# VFD_alpha_Sheet2.net
KiCad netlist of a schematic drawn in Altium Designer
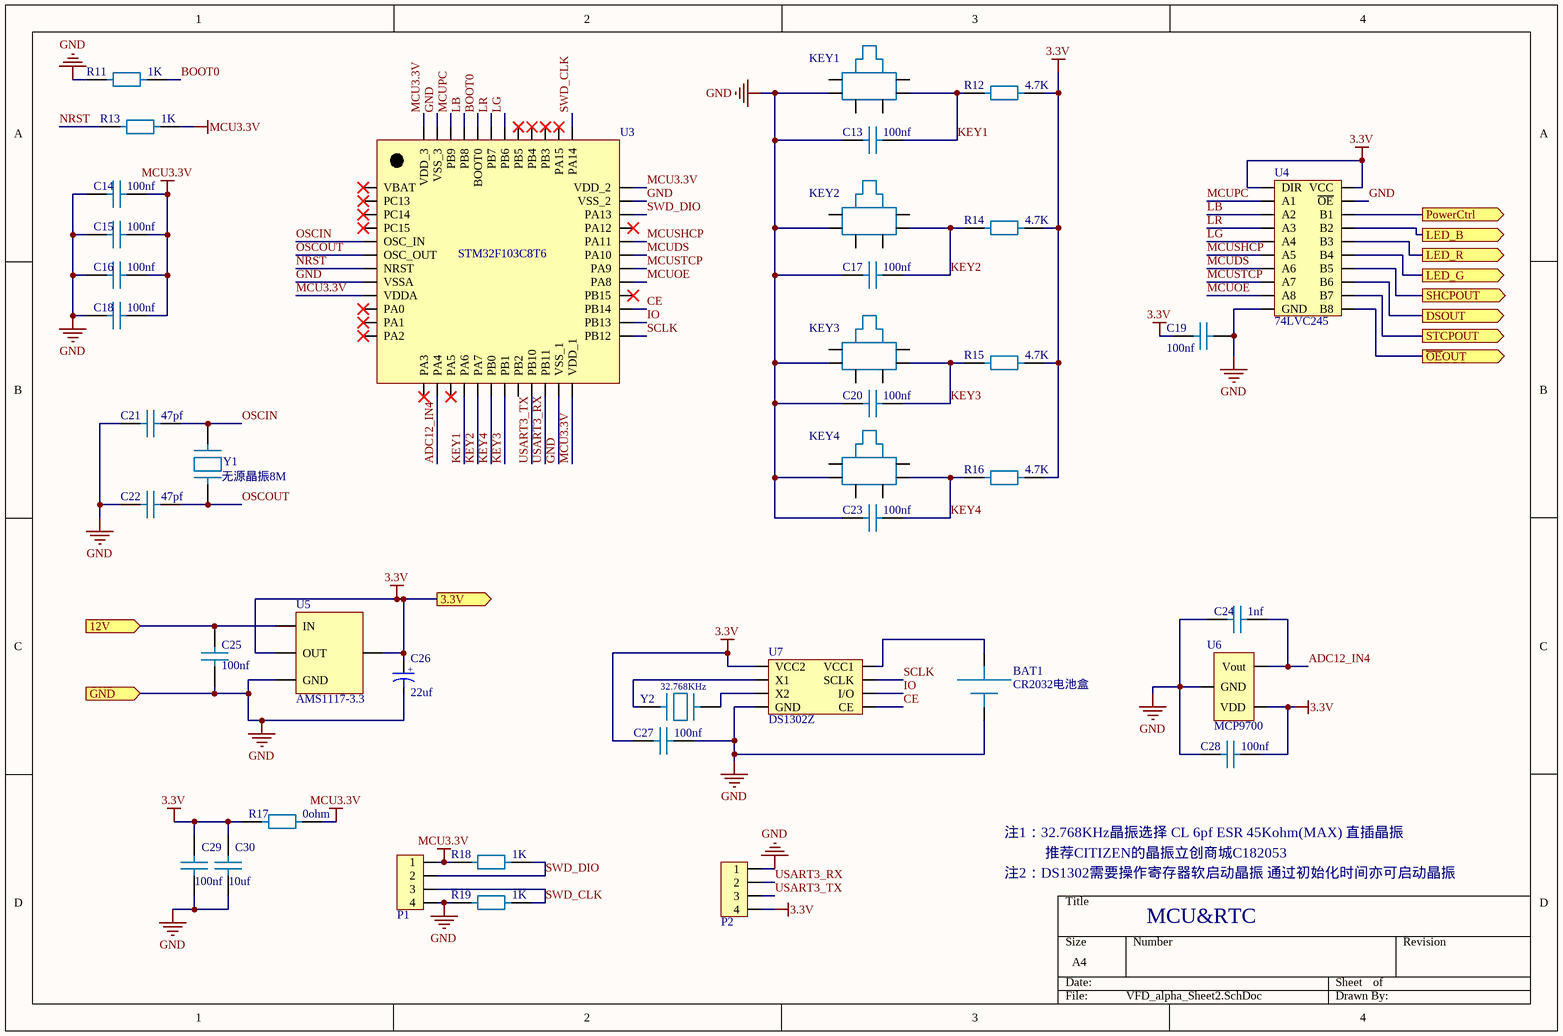
[diagram p0: VFD_alpha_Sheet2.SchDoc]

(export (version "E")
  (design (tool "Eeschema 10.0.6"))
  (components
    (comp (ref "BAT1")
      (value "CR2032电池盒")
      (footprint "SBAT-CR2032")
      (libsource (lib "ZZB_Lib") (part "CR2032电池盒"))
    )
    (comp (ref "C13")
      (value "100nf")
      (footprint "0603")
      (fields (field (name "Comment") "C"))
      (libsource (lib "ZZB_Lib") (part "C(0603)"))
    )
    (comp (ref "C14")
      (value "100nf")
      (footprint "0603")
      (fields (field (name "Comment") "C"))
      (libsource (lib "ZZB_Lib") (part "C(0603)"))
    )
    (comp (ref "C15")
      (value "100nf")
      (footprint "0603")
      (fields (field (name "Comment") "C"))
      (libsource (lib "ZZB_Lib") (part "C(0603)"))
    )
    (comp (ref "C16")
      (value "100nf")
      (footprint "0603")
      (fields (field (name "Comment") "C"))
      (libsource (lib "ZZB_Lib") (part "C(0603)"))
    )
    (comp (ref "C17")
      (value "100nf")
      (footprint "0603")
      (fields (field (name "Comment") "C"))
      (libsource (lib "ZZB_Lib") (part "C(0603)"))
    )
    (comp (ref "C18")
      (value "100nf")
      (footprint "0603")
      (fields (field (name "Comment") "C"))
      (libsource (lib "ZZB_Lib") (part "C(0603)"))
    )
    (comp (ref "C19")
      (value "100nf")
      (footprint "0603")
      (fields (field (name "Comment") "C"))
      (libsource (lib "ZZB_Lib") (part "C(0603)"))
    )
    (comp (ref "C20")
      (value "100nf")
      (footprint "0603")
      (fields (field (name "Comment") "C"))
      (libsource (lib "ZZB_Lib") (part "C(0603)"))
    )
    (comp (ref "C21")
      (value "47pf")
      (footprint "0603")
      (fields (field (name "Comment") "C"))
      (libsource (lib "ZZB_Lib") (part "C(0603)"))
    )
    (comp (ref "C22")
      (value "47pf")
      (footprint "0603")
      (fields (field (name "Comment") "C"))
      (libsource (lib "ZZB_Lib") (part "C(0603)"))
    )
    (comp (ref "C23")
      (value "100nf")
      (footprint "0603")
      (fields (field (name "Comment") "C"))
      (libsource (lib "ZZB_Lib") (part "C(0603)"))
    )
    (comp (ref "C24")
      (value "1nf")
      (footprint "0603")
      (fields (field (name "Comment") "C"))
      (libsource (lib "ZZB_Lib") (part "C(0603)"))
    )
    (comp (ref "C25")
      (value "100nf")
      (footprint "0805")
      (fields (field (name "Comment") "C(0805)"))
      (libsource (lib "ZZB_Lib") (part "C(0805)"))
    )
    (comp (ref "C26")
      (value "22uf")
      (footprint "CAPCP3216X06N")
      (fields (field (name "Comment") "钽电容"))
      (libsource (lib "ZZB_Lib") (part "钽电容(3216)"))
    )
    (comp (ref "C27")
      (value "100nf")
      (footprint "0603")
      (fields (field (name "Comment") "C"))
      (libsource (lib "ZZB_Lib") (part "C(0603)"))
    )
    (comp (ref "C28")
      (value "100nf")
      (footprint "0603")
      (fields (field (name "Comment") "C"))
      (libsource (lib "ZZB_Lib") (part "C(0603)"))
    )
    (comp (ref "C29")
      (value "100nf")
      (footprint "0603")
      (fields (field (name "Comment") "C"))
      (libsource (lib "ZZB_Lib") (part "C(0603)"))
    )
    (comp (ref "C30")
      (value "10uf")
      (footprint "0603")
      (fields (field (name "Comment") "C"))
      (libsource (lib "ZZB_Lib") (part "C(0603)"))
    )
    (comp (ref "KEY1") (value "无锁按键") (footprint "侧面按键") (libsource (lib "ZZB_Lib") (part "无锁按键")))
    (comp (ref "KEY2") (value "无锁按键") (footprint "侧面按键") (libsource (lib "ZZB_Lib") (part "无锁按键")))
    (comp (ref "KEY3") (value "无锁按键") (footprint "侧面按键") (libsource (lib "ZZB_Lib") (part "无锁按键")))
    (comp (ref "KEY4") (value "无锁按键") (footprint "侧面按键") (libsource (lib "ZZB_Lib") (part "无锁按键")))
    (comp (ref "P1") (value "连接器4P") (footprint "Connector4P") (libsource (lib "ZZB_Lib") (part "连接器4P")))
    (comp (ref "P2") (value "连接器4P") (footprint "Connector4P") (libsource (lib "ZZB_Lib") (part "连接器4P")))
    (comp (ref "R11")
      (value "1K")
      (footprint "0603")
      (fields (field (name "Comment") "R"))
      (libsource (lib "ZZB_Lib") (part "R(0603)"))
    )
    (comp (ref "R12")
      (value "4.7K")
      (footprint "0603")
      (fields (field (name "Comment") "R"))
      (libsource (lib "ZZB_Lib") (part "R(0603)"))
    )
    (comp (ref "R13")
      (value "1K")
      (footprint "0603")
      (fields (field (name "Comment") "R"))
      (libsource (lib "ZZB_Lib") (part "R(0603)"))
    )
    (comp (ref "R14")
      (value "4.7K")
      (footprint "0603")
      (fields (field (name "Comment") "R"))
      (libsource (lib "ZZB_Lib") (part "R(0603)"))
    )
    (comp (ref "R15")
      (value "4.7K")
      (footprint "0603")
      (fields (field (name "Comment") "R"))
      (libsource (lib "ZZB_Lib") (part "R(0603)"))
    )
    (comp (ref "R16")
      (value "4.7K")
      (footprint "0603")
      (fields (field (name "Comment") "R"))
      (libsource (lib "ZZB_Lib") (part "R(0603)"))
    )
    (comp (ref "R17")
      (value "0ohm")
      (footprint "0603")
      (fields (field (name "Comment") "R"))
      (libsource (lib "ZZB_Lib") (part "R(0603)"))
    )
    (comp (ref "R18")
      (value "1K")
      (footprint "0603")
      (fields (field (name "Comment") "R"))
      (libsource (lib "ZZB_Lib") (part "R(0603)"))
    )
    (comp (ref "R19")
      (value "1K")
      (footprint "0603")
      (fields (field (name "Comment") "R"))
      (libsource (lib "ZZB_Lib") (part "R(0603)"))
    )
    (comp (ref "U3")
      (value "STM32F103C8T6")
      (footprint "STM32F103x8LQFP48")
      (libsource (lib "ZZB_Lib") (part "STM32F103C8T6"))
    )
    (comp (ref "U4")
      (value "74LVC245")
      (footprint "TSOP-20N-74LVC245")
      (libsource (lib "ZZB_Lib") (part "74LVC245"))
    )
    (comp (ref "U5")
      (value "AMS1117-3.3")
      (footprint "AMS1117-3.3")
      (libsource (lib "ZZB_Lib") (part "AMS1117-X"))
    )
    (comp (ref "U6")
      (value "MCP9700")
      (footprint "SOT-23-s8550")
      (libsource (lib "ZZB_Lib") (part "MCP9700"))
    )
    (comp (ref "U7")
      (value "DS1302Z")
      (footprint "SOIC-8P DS1302Z")
      (libsource (lib "ZZB_Lib") (part "DS1302Z"))
    )
    (comp (ref "Y1") (value "无源晶振8M") (footprint "晶振8M") (libsource (lib "ZZB_Lib") (part "无源晶振8M")))
    (comp (ref "Y2")
      (value "直插无源晶振32.768KHz")
      (footprint "2*6_OSC")
      (libsource (lib "ZZB_Lib") (part "直插无源晶振32.768KHz"))
    )
  )
  (nets
    (net (code "1") (name "/12V") (class "Default")
      (node (ref "C25") (pin "2") (pinfunction "2_2") (pintype "passive"))
      (node (ref "U5") (pin "3") (pinfunction "IN_3") (pintype "passive"))
    )
    (net (code "2") (name "/ADC12_IN4") (class "Default")
      (node (ref "C24") (pin "2") (pinfunction "2_2") (pintype "passive"))
      (node (ref "U3") (pin "14") (pinfunction "PA4_14") (pintype "passive"))
      (node (ref "U6") (pin "3") (pinfunction "Vout_3") (pintype "passive"))
    )
    (net (code "3") (name "/BOOT0") (class "Default")
      (node (ref "R11") (pin "1") (pinfunction "1_1") (pintype "passive"))
      (node (ref "U3") (pin "44") (pinfunction "BOOT0_44") (pintype "passive"))
    )
    (net (code "4") (name "/CE") (class "Default")
      (node (ref "U3") (pin "27") (pinfunction "PB14_27") (pintype "passive"))
      (node (ref "U7") (pin "5") (pinfunction "CE_5") (pintype "passive"))
    )
    (net (code "5") (name "/DSOUT") (class "Default")
      (node (ref "U4") (pin "13") (pinfunction "B6_13") (pintype "passive"))
    )
    (net (code "6") (name "/IO") (class "Default")
      (node (ref "U3") (pin "26") (pinfunction "PB13_26") (pintype "passive"))
      (node (ref "U7") (pin "6") (pinfunction "I/O_6") (pintype "passive"))
    )
    (net (code "7") (name "/KEY1") (class "Default")
      (node (ref "C13") (pin "2") (pinfunction "2_2") (pintype "passive"))
      (node (ref "KEY1") (pin "5") (pinfunction "5_5") (pintype "passive"))
      (node (ref "R12") (pin "1") (pinfunction "1_1") (pintype "passive"))
      (node (ref "U3") (pin "16") (pinfunction "PA6_16") (pintype "passive"))
    )
    (net (code "8") (name "/KEY2") (class "Default")
      (node (ref "C17") (pin "2") (pinfunction "2_2") (pintype "passive"))
      (node (ref "KEY2") (pin "5") (pinfunction "5_5") (pintype "passive"))
      (node (ref "R14") (pin "1") (pinfunction "1_1") (pintype "passive"))
      (node (ref "U3") (pin "17") (pinfunction "PA7_17") (pintype "passive"))
    )
    (net (code "9") (name "/KEY3") (class "Default")
      (node (ref "C20") (pin "2") (pinfunction "2_2") (pintype "passive"))
      (node (ref "KEY3") (pin "5") (pinfunction "5_5") (pintype "passive"))
      (node (ref "R15") (pin "1") (pinfunction "1_1") (pintype "passive"))
      (node (ref "U3") (pin "19") (pinfunction "PB1_19") (pintype "passive"))
    )
    (net (code "10") (name "/KEY4") (class "Default")
      (node (ref "C23") (pin "2") (pinfunction "2_2") (pintype "passive"))
      (node (ref "KEY4") (pin "5") (pinfunction "5_5") (pintype "passive"))
      (node (ref "R16") (pin "1") (pinfunction "1_1") (pintype "passive"))
      (node (ref "U3") (pin "18") (pinfunction "PB0_18") (pintype "passive"))
    )
    (net (code "11") (name "/LB") (class "Default")
      (node (ref "U3") (pin "45") (pinfunction "PB8_45") (pintype "passive"))
      (node (ref "U4") (pin "3") (pinfunction "A2_3") (pintype "passive"))
    )
    (net (code "12") (name "/LED_B") (class "Default")
      (node (ref "U4") (pin "17") (pinfunction "B2_17") (pintype "passive"))
    )
    (net (code "13") (name "/LED_G") (class "Default")
      (node (ref "U4") (pin "15") (pinfunction "B4_15") (pintype "passive"))
    )
    (net (code "14") (name "/LED_R") (class "Default")
      (node (ref "U4") (pin "16") (pinfunction "B3_16") (pintype "passive"))
    )
    (net (code "15") (name "/LG") (class "Default")
      (node (ref "U3") (pin "42") (pinfunction "PB6_42") (pintype "passive"))
      (node (ref "U4") (pin "5") (pinfunction "A4_5") (pintype "passive"))
    )
    (net (code "16") (name "/LR") (class "Default")
      (node (ref "U3") (pin "43") (pinfunction "PB7_43") (pintype "passive"))
      (node (ref "U4") (pin "4") (pinfunction "A3_4") (pintype "passive"))
    )
    (net (code "17") (name "/MCUDS") (class "Default")
      (node (ref "U3") (pin "31") (pinfunction "PA10_31") (pintype "passive"))
      (node (ref "U4") (pin "7") (pinfunction "A6_7") (pintype "passive"))
    )
    (net (code "18") (name "/MCUOE") (class "Default")
      (node (ref "U3") (pin "29") (pinfunction "PA8_29") (pintype "passive"))
      (node (ref "U4") (pin "9") (pinfunction "A8_9") (pintype "passive"))
    )
    (net (code "19") (name "/MCUPC") (class "Default")
      (node (ref "U3") (pin "46") (pinfunction "PB9_46") (pintype "passive"))
      (node (ref "U4") (pin "2") (pinfunction "A1_2") (pintype "passive"))
    )
    (net (code "20") (name "/MCUSHCP") (class "Default")
      (node (ref "U3") (pin "32") (pinfunction "PA11_32") (pintype "passive"))
      (node (ref "U4") (pin "6") (pinfunction "A5_6") (pintype "passive"))
    )
    (net (code "21") (name "/MCUSTCP") (class "Default")
      (node (ref "U3") (pin "30") (pinfunction "PA9_30") (pintype "passive"))
      (node (ref "U4") (pin "8") (pinfunction "A7_8") (pintype "passive"))
    )
    (net (code "22") (name "/NRST") (class "Default")
      (node (ref "R13") (pin "1") (pinfunction "1_1") (pintype "passive"))
      (node (ref "U3") (pin "7") (pinfunction "NRST_7") (pintype "passive"))
    )
    (net (code "23") (name "/OSCIN") (class "Default")
      (node (ref "C21") (pin "2") (pinfunction "2_2") (pintype "passive"))
      (node (ref "U3") (pin "5") (pinfunction "OSC_IN_5") (pintype "passive"))
      (node (ref "Y1") (pin "2") (pinfunction "2_2") (pintype "passive"))
    )
    (net (code "24") (name "/OSCOUT") (class "Default")
      (node (ref "C22") (pin "2") (pinfunction "2_2") (pintype "passive"))
      (node (ref "U3") (pin "6") (pinfunction "OSC_OUT_6") (pintype "passive"))
      (node (ref "Y1") (pin "1") (pinfunction "1_1") (pintype "passive"))
    )
    (net (code "25") (name "/PowerCtrl") (class "Default")
      (node (ref "U4") (pin "18") (pinfunction "B1_18") (pintype "passive"))
    )
    (net (code "26") (name "/SCLK") (class "Default")
      (node (ref "U3") (pin "25") (pinfunction "PB12_25") (pintype "passive"))
      (node (ref "U7") (pin "7") (pinfunction "SCLK_7") (pintype "passive"))
    )
    (net (code "27") (name "/SHCPOUT") (class "Default")
      (node (ref "U4") (pin "14") (pinfunction "B5_14") (pintype "passive"))
    )
    (net (code "28") (name "/STCPOUT") (class "Default")
      (node (ref "U4") (pin "12") (pinfunction "B7_12") (pintype "passive"))
    )
    (net (code "29") (name "/SWD_CLK") (class "Default")
      (node (ref "P1") (pin "3") (pinfunction "3_3") (pintype "passive"))
      (node (ref "R19") (pin "2") (pinfunction "2_2") (pintype "passive"))
      (node (ref "U3") (pin "37") (pinfunction "PA14_37") (pintype "passive"))
    )
    (net (code "30") (name "/SWD_DIO") (class "Default")
      (node (ref "P1") (pin "2") (pinfunction "2_2") (pintype "passive"))
      (node (ref "R18") (pin "1") (pinfunction "1_1") (pintype "passive"))
      (node (ref "U3") (pin "34") (pinfunction "PA13_34") (pintype "passive"))
    )
    (net (code "31") (name "/USART3_RX") (class "Default")
      (node (ref "P2") (pin "2") (pinfunction "2_2") (pintype "passive"))
      (node (ref "U3") (pin "22") (pinfunction "PB11_22") (pintype "passive"))
    )
    (net (code "32") (name "/USART3_TX") (class "Default")
      (node (ref "P2") (pin "3") (pinfunction "3_3") (pintype "passive"))
      (node (ref "U3") (pin "21") (pinfunction "PB10_21") (pintype "passive"))
    )
    (net (code "33") (name "/~{OE}OUT") (class "Default")
      (node (ref "U4") (pin "11") (pinfunction "B8_11") (pintype "passive"))
    )
    (net (code "34") (name "3.3V") (class "Default")
      (node (ref "C19") (pin "1") (pinfunction "1_1") (pintype "passive"))
      (node (ref "C26") (pin "1") (pinfunction "1_1") (pintype "passive"))
      (node (ref "C27") (pin "1") (pinfunction "1_1") (pintype "passive"))
      (node (ref "C28") (pin "2") (pinfunction "2_2") (pintype "passive"))
      (node (ref "C29") (pin "2") (pinfunction "2_2") (pintype "passive"))
      (node (ref "C30") (pin "2") (pinfunction "2_2") (pintype "passive"))
      (node (ref "P2") (pin "4") (pinfunction "4_4") (pintype "passive"))
      (node (ref "R12") (pin "2") (pinfunction "2_2") (pintype "passive"))
      (node (ref "R14") (pin "2") (pinfunction "2_2") (pintype "passive"))
      (node (ref "R15") (pin "2") (pinfunction "2_2") (pintype "passive"))
      (node (ref "R16") (pin "2") (pinfunction "2_2") (pintype "passive"))
      (node (ref "R17") (pin "1") (pinfunction "1_1") (pintype "passive"))
      (node (ref "U4") (pin "1") (pinfunction "DIR_1") (pintype "passive"))
      (node (ref "U4") (pin "20") (pinfunction "VCC_20") (pintype "passive"))
      (node (ref "U5") (pin "2") (pinfunction "OUT_2") (pintype "passive"))
      (node (ref "U5") (pin "4") (pintype "passive"))
      (node (ref "U6") (pin "1") (pinfunction "VDD_1") (pintype "passive"))
      (node (ref "U7") (pin "1") (pinfunction "VCC2_1") (pintype "passive"))
    )
    (net (code "35") (name "GND") (class "Default")
      (node (ref "BAT1") (pin "1") (pinfunction "1_1") (pintype "passive"))
      (node (ref "C13") (pin "1") (pinfunction "1_1") (pintype "passive"))
      (node (ref "C14") (pin "1") (pinfunction "1_1") (pintype "passive"))
      (node (ref "C15") (pin "1") (pinfunction "1_1") (pintype "passive"))
      (node (ref "C16") (pin "1") (pinfunction "1_1") (pintype "passive"))
      (node (ref "C17") (pin "1") (pinfunction "1_1") (pintype "passive"))
      (node (ref "C18") (pin "1") (pinfunction "1_1") (pintype "passive"))
      (node (ref "C19") (pin "2") (pinfunction "2_2") (pintype "passive"))
      (node (ref "C20") (pin "1") (pinfunction "1_1") (pintype "passive"))
      (node (ref "C21") (pin "1") (pinfunction "1_1") (pintype "passive"))
      (node (ref "C22") (pin "1") (pinfunction "1_1") (pintype "passive"))
      (node (ref "C23") (pin "1") (pinfunction "1_1") (pintype "passive"))
      (node (ref "C24") (pin "1") (pinfunction "1_1") (pintype "passive"))
      (node (ref "C25") (pin "1") (pinfunction "1_1") (pintype "passive"))
      (node (ref "C26") (pin "2") (pinfunction "2_2") (pintype "passive"))
      (node (ref "C27") (pin "2") (pinfunction "2_2") (pintype "passive"))
      (node (ref "C28") (pin "1") (pinfunction "1_1") (pintype "passive"))
      (node (ref "C29") (pin "1") (pinfunction "1_1") (pintype "passive"))
      (node (ref "C30") (pin "1") (pinfunction "1_1") (pintype "passive"))
      (node (ref "KEY1") (pin "2") (pinfunction "2_2") (pintype "passive"))
      (node (ref "KEY2") (pin "2") (pinfunction "2_2") (pintype "passive"))
      (node (ref "KEY3") (pin "2") (pinfunction "2_2") (pintype "passive"))
      (node (ref "KEY4") (pin "2") (pinfunction "2_2") (pintype "passive"))
      (node (ref "P1") (pin "4") (pinfunction "4_4") (pintype "passive"))
      (node (ref "P2") (pin "1") (pinfunction "1_1") (pintype "passive"))
      (node (ref "R11") (pin "2") (pinfunction "2_2") (pintype "passive"))
      (node (ref "R19") (pin "1") (pinfunction "1_1") (pintype "passive"))
      (node (ref "U3") (pin "23") (pinfunction "VSS_1_23") (pintype "passive"))
      (node (ref "U3") (pin "35") (pinfunction "VSS_2_35") (pintype "passive"))
      (node (ref "U3") (pin "47") (pinfunction "VSS_3_47") (pintype "passive"))
      (node (ref "U3") (pin "8") (pinfunction "VSSA_8") (pintype "passive"))
      (node (ref "U4") (pin "10") (pinfunction "GND_10") (pintype "passive"))
      (node (ref "U4") (pin "19") (pinfunction "~{OE}_19") (pintype "passive"))
      (node (ref "U5") (pin "1") (pinfunction "GND_1") (pintype "passive"))
      (node (ref "U6") (pin "2") (pinfunction "GND_2") (pintype "passive"))
      (node (ref "U7") (pin "4") (pinfunction "GND_4") (pintype "passive"))
    )
    (net (code "36") (name "MCU3.3V") (class "Default")
      (node (ref "C14") (pin "2") (pinfunction "2_2") (pintype "passive"))
      (node (ref "C15") (pin "2") (pinfunction "2_2") (pintype "passive"))
      (node (ref "C16") (pin "2") (pinfunction "2_2") (pintype "passive"))
      (node (ref "C18") (pin "2") (pinfunction "2_2") (pintype "passive"))
      (node (ref "P1") (pin "1") (pinfunction "1_1") (pintype "passive"))
      (node (ref "R13") (pin "2") (pinfunction "2_2") (pintype "passive"))
      (node (ref "R17") (pin "2") (pinfunction "2_2") (pintype "passive"))
      (node (ref "R18") (pin "2") (pinfunction "2_2") (pintype "passive"))
      (node (ref "U3") (pin "24") (pinfunction "VDD_1_24") (pintype "passive"))
      (node (ref "U3") (pin "36") (pinfunction "VDD_2_36") (pintype "passive"))
      (node (ref "U3") (pin "48") (pinfunction "VDD_3_48") (pintype "passive"))
      (node (ref "U3") (pin "9") (pinfunction "VDDA_9") (pintype "passive"))
    )
    (net (code "37") (name "Net-(U7-VCC1)") (class "Default")
      (node (ref "BAT1") (pin "2") (pinfunction "2_2") (pintype "passive"))
      (node (ref "U7") (pin "8") (pinfunction "VCC1_8") (pintype "passive"))
    )
    (net (code "38") (name "Net-(U7-X1)") (class "Default")
      (node (ref "U7") (pin "2") (pinfunction "X1_2") (pintype "passive"))
      (node (ref "Y2") (pin "1") (pinfunction "1_1") (pintype "passive"))
    )
    (net (code "39") (name "Net-(U7-X2)") (class "Default")
      (node (ref "U7") (pin "3") (pinfunction "X2_3") (pintype "passive"))
      (node (ref "Y2") (pin "2") (pinfunction "2_2") (pintype "passive"))
    )
    (net (code "40") (name "unconnected-(KEY1-Pad1)") (class "Default")
      (node (ref "KEY1") (pin "1") (pinfunction "1_1") (pintype "passive"))
    )
    (net (code "41") (name "unconnected-(KEY1-Pad3)") (class "Default")
      (node (ref "KEY1") (pin "3") (pinfunction "3_3") (pintype "passive"))
    )
    (net (code "42") (name "unconnected-(KEY1-Pad4)") (class "Default")
      (node (ref "KEY1") (pin "4") (pinfunction "4_4") (pintype "passive"))
    )
    (net (code "43") (name "unconnected-(KEY1-Pad6)") (class "Default")
      (node (ref "KEY1") (pin "6") (pinfunction "6_6") (pintype "passive"))
    )
    (net (code "44") (name "unconnected-(KEY2-Pad1)") (class "Default")
      (node (ref "KEY2") (pin "1") (pinfunction "1_1") (pintype "passive"))
    )
    (net (code "45") (name "unconnected-(KEY2-Pad3)") (class "Default")
      (node (ref "KEY2") (pin "3") (pinfunction "3_3") (pintype "passive"))
    )
    (net (code "46") (name "unconnected-(KEY2-Pad4)") (class "Default")
      (node (ref "KEY2") (pin "4") (pinfunction "4_4") (pintype "passive"))
    )
    (net (code "47") (name "unconnected-(KEY2-Pad6)") (class "Default")
      (node (ref "KEY2") (pin "6") (pinfunction "6_6") (pintype "passive"))
    )
    (net (code "48") (name "unconnected-(KEY3-Pad1)") (class "Default")
      (node (ref "KEY3") (pin "1") (pinfunction "1_1") (pintype "passive"))
    )
    (net (code "49") (name "unconnected-(KEY3-Pad3)") (class "Default")
      (node (ref "KEY3") (pin "3") (pinfunction "3_3") (pintype "passive"))
    )
    (net (code "50") (name "unconnected-(KEY3-Pad4)") (class "Default")
      (node (ref "KEY3") (pin "4") (pinfunction "4_4") (pintype "passive"))
    )
    (net (code "51") (name "unconnected-(KEY3-Pad6)") (class "Default")
      (node (ref "KEY3") (pin "6") (pinfunction "6_6") (pintype "passive"))
    )
    (net (code "52") (name "unconnected-(KEY4-Pad1)") (class "Default")
      (node (ref "KEY4") (pin "1") (pinfunction "1_1") (pintype "passive"))
    )
    (net (code "53") (name "unconnected-(KEY4-Pad3)") (class "Default")
      (node (ref "KEY4") (pin "3") (pinfunction "3_3") (pintype "passive"))
    )
    (net (code "54") (name "unconnected-(KEY4-Pad4)") (class "Default")
      (node (ref "KEY4") (pin "4") (pinfunction "4_4") (pintype "passive"))
    )
    (net (code "55") (name "unconnected-(KEY4-Pad6)") (class "Default")
      (node (ref "KEY4") (pin "6") (pinfunction "6_6") (pintype "passive"))
    )
    (net (code "56") (name "unconnected-(U3-PA0-Pad10)") (class "Default")
      (node (ref "U3") (pin "10") (pinfunction "PA0_10") (pintype "passive+no_connect"))
    )
    (net (code "57") (name "unconnected-(U3-PA1-Pad11)") (class "Default")
      (node (ref "U3") (pin "11") (pinfunction "PA1_11") (pintype "passive+no_connect"))
    )
    (net (code "58") (name "unconnected-(U3-PA2-Pad12)") (class "Default")
      (node (ref "U3") (pin "12") (pinfunction "PA2_12") (pintype "passive+no_connect"))
    )
    (net (code "59") (name "unconnected-(U3-PA3-Pad13)") (class "Default")
      (node (ref "U3") (pin "13") (pinfunction "PA3_13") (pintype "passive+no_connect"))
    )
    (net (code "60") (name "unconnected-(U3-PA5-Pad15)") (class "Default")
      (node (ref "U3") (pin "15") (pinfunction "PA5_15") (pintype "passive+no_connect"))
    )
    (net (code "61") (name "unconnected-(U3-PA12-Pad33)") (class "Default")
      (node (ref "U3") (pin "33") (pinfunction "PA12_33") (pintype "passive+no_connect"))
    )
    (net (code "62") (name "unconnected-(U3-PA15-Pad38)") (class "Default")
      (node (ref "U3") (pin "38") (pinfunction "PA15_38") (pintype "passive+no_connect"))
    )
    (net (code "63") (name "unconnected-(U3-PB2-Pad20)") (class "Default")
      (node (ref "U3") (pin "20") (pinfunction "PB2_20") (pintype "passive"))
    )
    (net (code "64") (name "unconnected-(U3-PB3-Pad39)") (class "Default")
      (node (ref "U3") (pin "39") (pinfunction "PB3_39") (pintype "passive+no_connect"))
    )
    (net (code "65") (name "unconnected-(U3-PB4-Pad40)") (class "Default")
      (node (ref "U3") (pin "40") (pinfunction "PB4_40") (pintype "passive+no_connect"))
    )
    (net (code "66") (name "unconnected-(U3-PB5-Pad41)") (class "Default")
      (node (ref "U3") (pin "41") (pinfunction "PB5_41") (pintype "passive+no_connect"))
    )
    (net (code "67") (name "unconnected-(U3-PB15-Pad28)") (class "Default")
      (node (ref "U3") (pin "28") (pinfunction "PB15_28") (pintype "passive+no_connect"))
    )
    (net (code "68") (name "unconnected-(U3-PC13-Pad2)") (class "Default")
      (node (ref "U3") (pin "2") (pinfunction "PC13_2") (pintype "passive+no_connect"))
    )
    (net (code "69") (name "unconnected-(U3-PC14-Pad3)") (class "Default")
      (node (ref "U3") (pin "3") (pinfunction "PC14_3") (pintype "passive+no_connect"))
    )
    (net (code "70") (name "unconnected-(U3-PC15-Pad4)") (class "Default")
      (node (ref "U3") (pin "4") (pinfunction "PC15_4") (pintype "passive+no_connect"))
    )
    (net (code "71") (name "unconnected-(U3-VBAT-Pad1)") (class "Default")
      (node (ref "U3") (pin "1") (pinfunction "VBAT_1") (pintype "passive+no_connect"))
    )
  )
)
